# Output.net
KiCad netlist of a schematic drawn in Altium Designer
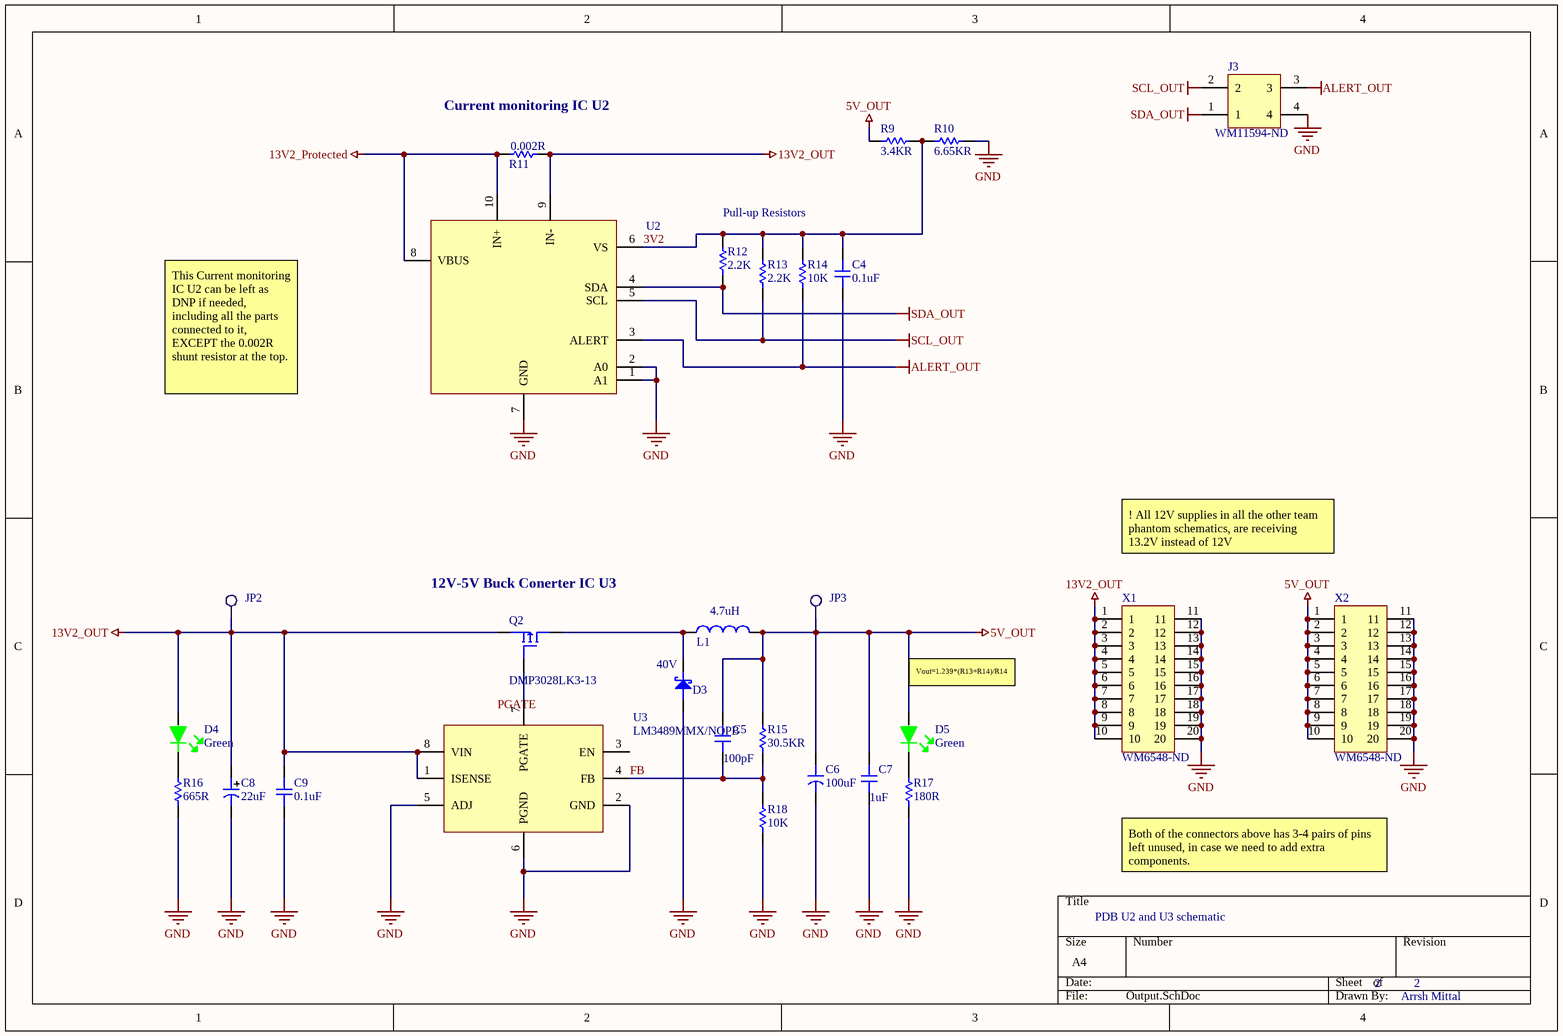
[diagram p0: Output.SchDoc]

(export (version "E")
  (design (tool "Eeschema 10.0.6"))
  (components
    (comp (ref "C4")
      (value "0.1uF")
      (footprint "CAP-0805")
      (description "CAP CER 0.1UF 16V Y5V 0805")
      (fields
        (field (name "MANUFACTURER") "KEMET")
        (field (name "MANUFACTURER PART NUMBER") "C0805C104Z4VACTU")
      )
      (libsource (lib "Capacitors") (part "0805-0.1uF-16V"))
    )
    (comp (ref "C5")
      (value "100pF")
      (description "0603 100 pF 50 V ±5% Tolerance C0G/NP0 SMT Multilayer Ceramic Capacitor")
      (fields
        (field (name "MANUFACTURER") "Kyocera AVX")
        (field (name "MANUFACTURER PART NUMBER") "06035A101JAT2~{A}4K")
      )
      (libsource (lib "Capacitors") (part "0603-100pF-50V"))
    )
    (comp (ref "C6")
      (value "100uF")
      (footprint "CAP-1411")
      (description "CAP TANT 100UF 10% 6.3V 1411")
      (fields
        (field (name "MANUFACTURER") "KEMET")
        (field (name "MANUFACTURER PART NUMBER") "T495B107K006ATE400")
      )
      (libsource (lib "Capacitors") (part "1411-100uF-6.3V"))
    )
    (comp (ref "C7")
      (value "1uF")
      (footprint "CAP-0603")
      (description "CAP CER 1UF 16V X7R 0603")
      (fields
        (field (name "MANUFACTURER") "KEMET")
        (field (name "MANUFACTURER PART NUMBER") "C0603C105K4RACTU")
      )
      (libsource (lib "Capacitors") (part "0603-1uF-16V"))
    )
    (comp (ref "C8")
      (value "22uF")
      (description "Aluminum Electrolytic Capacitors - SMD 22uF 50 Volts 20% LYTICS/IC")
      (fields
        (field (name "MANUFACTURER") "CDE Illinois Capacitor")
        (field (name "MANUFACTURER PART NUMBER") "226SML050M")
      )
      (libsource (lib "Capacitors") (part "AEC-22uF-50V"))
    )
    (comp (ref "C9")
      (value "0.1uF")
      (footprint "CAP-0805")
      (description "CAP CER 0.1UF 50V Y5V 0805")
      (fields
        (field (name "MANUFACTURER") "KEMET")
        (field (name "MANUFACTURER PART NUMBER") "C0805C104Z5VACTU")
      )
      (libsource (lib "Capacitors") (part "0805-0.1uF-50V"))
    )
    (comp (ref "D3")
      (value "40V")
      (description "DIODE SCHOTTKY 40V 8A DO214AB")
      (fields (field (name "MANUFACTURER") "MCC") (field (name "MANUFACTURER PART NUMBER") "SK84L-TP"))
      (libsource (lib "Diodes") (part "Schottky-40V-8A"))
    )
    (comp (ref "D4")
      (value "Green")
      (footprint "LED-0603")
      (description "LED GREEN CLEAR 0603 SMD")
      (fields
        (field (name "MANUFACTURER") "Wurth Electronics")
        (field (name "MANUFACTURER PART NUMBER") "150060VS75000")
      )
      (libsource (lib "LEDs") (part "LED-Green"))
    )
    (comp (ref "D5")
      (value "Green")
      (footprint "LED-0603")
      (description "LED GREEN CLEAR 0603 SMD")
      (fields
        (field (name "MANUFACTURER") "Wurth Electronics")
        (field (name "MANUFACTURER PART NUMBER") "150060VS75000")
      )
      (libsource (lib "LEDs") (part "LED-Green"))
    )
    (comp (ref "J3")
      (value "WM11594-ND")
      (footprint "2X2PIN")
      (description "CONN HEADER R/A 4POS 3.5MM")
      (fields (field (name "MANUFACTURER") "Molex") (field (name "MANUFACTURER PART NUMBER") "172316-1104"))
      (libsource (lib "Connectors") (part "2X2PIN"))
    )
    (comp (ref "JP2")
      (value "Testpoint2")
      (footprint "TP2")
      (description "Single layer pad TP")
      (libsource (lib "Misc") (part "Testpoint2"))
    )
    (comp (ref "JP3")
      (value "Testpoint2")
      (footprint "TP2")
      (description "Single layer pad TP")
      (libsource (lib "Misc") (part "Testpoint2"))
    )
    (comp (ref "L1")
      (value "4.7uH")
      (description "FIXED IND 4.7UH 10A 15.5 MOHM")
      (fields (field (name "MANUFACTURER") "Pulse") (field (name "MANUFACTURER PART NUMBER") "PA4342.472NLT"))
      (libsource (lib "Inductors") (part "4.7uH-10A"))
    )
    (comp (ref "Q2")
      (value "DMP3028LK3-13")
      (footprint "DPAK228P990X239-4N")
      (description "MOSFET P-CH 30V 27A TO252")
      (fields (field (name "MANUFACTURER") "Diodes"))
      (libsource (lib "Transistors") (part "P-FET-30V-27A"))
    )
    (comp (ref "R9")
      (value "3.4KR")
      (footprint "RESC1608X50N")
      (description "Res Thin Film 0603 3.4K Ohm 0.1% 1/10W ±25ppm/°C Molded SMD Paper T/R")
      (fields
        (field (name "MANUFACTURER") "TE Connectivity")
        (field (name "MANUFACTURER PART NUMBER") "RP73PF1J3K4BTDF")
      )
      (libsource (lib "Resistors") (part "0603-3.4KR"))
    )
    (comp (ref "R10")
      (value "6.65KR")
      (footprint "RESC1608X50N")
      (description "RES SMD 6.65K OHM 0.1% 1/6W 0603")
      (fields
        (field (name "MANUFACTURER") "TE Connectivity")
        (field (name "MANUFACTURER PART NUMBER") "8-2176088-4")
      )
      (libsource (lib "Resistors") (part "0603-6.65KR"))
    )
    (comp (ref "R11")
      (value "0.002R")
      (footprint "2512")
      (fields
        (field (name "MANUFACTURER") "Bourns")
        (field (name "MANUFACTURER PART NUMBER") "CSS2H-2512K-2L00F")
        (field (name "TOLERANCE") "1%")
      )
      (libsource (lib "Resistors") (part "2512-0.002R-5W"))
    )
    (comp (ref "R12")
      (value "2.2K")
      (footprint "RES-0603")
      (description "RES SMD 2.2K OHM 1% 1/10W 0603")
      (fields
        (field (name "MANUFACTURER") "Yageo Phycomp")
        (field (name "MANUFACTURER PART NUMBER") "RC0603FR-072K2L")
      )
      (libsource (lib "Resistors") (part "0603-2.2KR"))
    )
    (comp (ref "R13")
      (value "2.2K")
      (footprint "RES-0603")
      (description "RES SMD 2.2K OHM 1% 1/10W 0603")
      (fields
        (field (name "MANUFACTURER") "Yageo Phycomp")
        (field (name "MANUFACTURER PART NUMBER") "RC0603FR-072K2L")
      )
      (libsource (lib "Resistors") (part "0603-2.2KR"))
    )
    (comp (ref "R14")
      (value "10K")
      (footprint "RES-0603")
      (description "RES SMD 10K OHM 5% 1/10W 0603")
      (fields
        (field (name "MANUFACTURER") "Yageo")
        (field (name "MANUFACTURER PART NUMBER") "RC0603JR-0710KL")
      )
      (libsource (lib "Resistors") (part "0603-10KR"))
    )
    (comp (ref "R15")
      (value "30.5KR")
      (description "RES 30.5K OHM 1% 1/16W 0402")
      (fields
        (field (name "MANUFACTURER") "KOA Speer")
        (field (name "MANUFACTURER PART NUMBER") "RN73R1ETTP3052F25")
      )
      (libsource (lib "Resistors") (part "0402-30.5KR"))
    )
    (comp (ref "R16")
      (value "665R")
      (footprint "RES-0603")
      (description "RES SMD 665 OHM 1% 1/10W 0603")
      (fields
        (field (name "MANUFACTURER") "Yageo")
        (field (name "MANUFACTURER PART NUMBER") "RC0603FR-07665RL")
      )
      (libsource (lib "Resistors") (part "0603-665R"))
    )
    (comp (ref "R17")
      (value "180R")
      (footprint "RES-0603")
      (description "RES SMD 180 OHM 1% 1/10W 0603")
      (fields
        (field (name "MANUFACTURER") "TE Connectivity")
        (field (name "MANUFACTURER PART NUMBER") "CRGCQ0603F180R")
      )
      (libsource (lib "Resistors") (part "0603-180R"))
    )
    (comp (ref "R18")
      (value "10K")
      (footprint "RES-0402")
      (description "RES 10K OHM 1% 1/10W 0402")
      (fields
        (field (name "MANUFACTURER") "KOA Speer")
        (field (name "MANUFACTURER PART NUMBER") "RK73H1ETTP1002F")
      )
      (libsource (lib "Resistors") (part "0402-10KR"))
    )
    (comp (ref "U2")
      (value "INA226AIDGSR")
      (footprint "SOP50P490X110-10N:SOP50P490X110-10N")
      (description "Bi Directional Current and Power Monitor 10-Pin VSSOP T/R")
      (fields (field (name "MANUFACTURER") "Texas Instruments"))
      (libsource (lib "ICs") (part "INA226AIDGSR"))
    )
    (comp (ref "U3")
      (value "LM3489MMX/NOPB")
      (footprint "SOP65P490X110-8N")
      (description "DC DC Cntrlr Single-OUT Buck 4.5V to 35V Input 8-Pin VSSOP T/R")
      (fields (field (name "MANUFACTURER") "TI National Semiconductor"))
      (libsource (lib "ICs") (part "LM3489MMX/NOPB"))
    )
    (comp (ref "X1")
      (value "WM6548-ND")
      (footprint "MOLEX_20pin(RECT)")
      (description "Connector Header Through Hole 20 position 0.100\" (2.54mm)")
      (fields (field (name "SUPPLIER PART NUMBER 1") "WM6548-ND"))
      (libsource (lib "Connectors") (part "RECT_MOLEX_20pin"))
    )
    (comp (ref "X2")
      (value "WM6548-ND")
      (footprint "MOLEX_20pin(RECT)")
      (description "Connector Header Through Hole 20 position 0.100\" (2.54mm)")
      (fields (field (name "SUPPLIER PART NUMBER 1") "WM6548-ND"))
      (libsource (lib "Connectors") (part "RECT_MOLEX_20pin"))
    )
  )
  (nets
    (net (code "1") (name "/3V2") (class "Default")
      (node (ref "C4") (pin "2") (pinfunction "2_2") (pintype "passive"))
      (node (ref "R10") (pin "1") (pinfunction "1_1") (pintype "passive"))
      (node (ref "R12") (pin "2") (pinfunction "2_2") (pintype "passive"))
      (node (ref "R13") (pin "2") (pinfunction "2_2") (pintype "passive"))
      (node (ref "R14") (pin "2") (pinfunction "2_2") (pintype "passive"))
      (node (ref "R9") (pin "2") (pinfunction "2_2") (pintype "passive"))
      (node (ref "U2") (pin "6") (pinfunction "VS_6") (pintype "power_in"))
    )
    (net (code "3") (name "/FB") (class "Default")
      (node (ref "C5") (pin "1") (pinfunction "1_1") (pintype "passive"))
      (node (ref "R15") (pin "1") (pinfunction "1_1") (pintype "passive"))
      (node (ref "R18") (pin "2") (pinfunction "2_2") (pintype "passive"))
      (node (ref "U3") (pin "4") (pinfunction "FB_4") (pintype "power_in"))
    )
    (net (code "4") (name "5V_OUT") (class "Default")
      (node (ref "C5") (pin "2") (pinfunction "2_2") (pintype "passive"))
      (node (ref "C6") (pin "2") (pinfunction "2_2") (pintype "passive"))
      (node (ref "C7") (pin "2") (pinfunction "2_2") (pintype "passive"))
      (node (ref "D5") (pin "1") (pinfunction "1_1") (pintype "passive"))
      (node (ref "JP3") (pin "1") (pinfunction "1_1") (pintype "passive"))
      (node (ref "L1") (pin "2") (pinfunction "2_2") (pintype "passive"))
      (node (ref "R15") (pin "2") (pinfunction "2_2") (pintype "passive"))
      (node (ref "R9") (pin "1") (pinfunction "1_1") (pintype "passive"))
      (node (ref "X2") (pin "1") (pinfunction "1_1") (pintype "passive"))
      (node (ref "X2") (pin "10") (pinfunction "10_10") (pintype "passive"))
      (node (ref "X2") (pin "2") (pinfunction "2_2") (pintype "passive"))
      (node (ref "X2") (pin "3") (pinfunction "3_3") (pintype "passive"))
      (node (ref "X2") (pin "4") (pinfunction "4_4") (pintype "passive"))
      (node (ref "X2") (pin "5") (pinfunction "5_5") (pintype "passive"))
      (node (ref "X2") (pin "6") (pinfunction "6_6") (pintype "passive"))
      (node (ref "X2") (pin "7") (pinfunction "7_7") (pintype "passive"))
      (node (ref "X2") (pin "8") (pinfunction "8_8") (pintype "passive"))
      (node (ref "X2") (pin "9") (pinfunction "9_9") (pintype "passive"))
    )
    (net (code "5") (name "13V2_OUT") (class "Default")
      (node (ref "C8") (pin "1") (pinfunction "1_1") (pintype "passive"))
      (node (ref "C9") (pin "2") (pinfunction "2_2") (pintype "passive"))
      (node (ref "D4") (pin "1") (pinfunction "1_1") (pintype "passive"))
      (node (ref "JP2") (pin "1") (pinfunction "1_1") (pintype "passive"))
      (node (ref "Q2") (pin "3") (pinfunction "3_3") (pintype "passive"))
      (node (ref "R11") (pin "1") (pinfunction "1_1") (pintype "passive"))
      (node (ref "U2") (pin "9") (pinfunction "IN-_9") (pintype "power_in"))
      (node (ref "U3") (pin "1") (pinfunction "ISENSE_1") (pintype "power_in"))
      (node (ref "U3") (pin "8") (pinfunction "VIN_8") (pintype "power_in"))
      (node (ref "X1") (pin "1") (pinfunction "1_1") (pintype "passive"))
      (node (ref "X1") (pin "10") (pinfunction "10_10") (pintype "passive"))
      (node (ref "X1") (pin "2") (pinfunction "2_2") (pintype "passive"))
      (node (ref "X1") (pin "3") (pinfunction "3_3") (pintype "passive"))
      (node (ref "X1") (pin "4") (pinfunction "4_4") (pintype "passive"))
      (node (ref "X1") (pin "5") (pinfunction "5_5") (pintype "passive"))
      (node (ref "X1") (pin "6") (pinfunction "6_6") (pintype "passive"))
      (node (ref "X1") (pin "7") (pinfunction "7_7") (pintype "passive"))
      (node (ref "X1") (pin "8") (pinfunction "8_8") (pintype "passive"))
      (node (ref "X1") (pin "9") (pinfunction "9_9") (pintype "passive"))
    )
    (net (code "6") (name "13V2_Protected") (class "Default")
      (node (ref "R11") (pin "2") (pinfunction "2_2") (pintype "passive"))
      (node (ref "U2") (pin "10") (pinfunction "IN+_10") (pintype "power_in"))
      (node (ref "U2") (pin "8") (pinfunction "VBUS_8") (pintype "power_in"))
    )
    (net (code "7") (name "ALERT_OUT") (class "Default")
      (node (ref "J3") (pin "3") (pinfunction "3_3") (pintype "passive"))
      (node (ref "R14") (pin "1") (pinfunction "1_1") (pintype "passive"))
      (node (ref "U2") (pin "3") (pinfunction "ALERT_3") (pintype "power_in"))
    )
    (net (code "8") (name "GND") (class "Default")
      (node (ref "C4") (pin "1") (pinfunction "1_1") (pintype "passive"))
      (node (ref "C6") (pin "1") (pinfunction "1_1") (pintype "passive"))
      (node (ref "C7") (pin "1") (pinfunction "1_1") (pintype "passive"))
      (node (ref "C8") (pin "2") (pinfunction "2_2") (pintype "passive"))
      (node (ref "C9") (pin "1") (pinfunction "1_1") (pintype "passive"))
      (node (ref "D3") (pin "2") (pinfunction "2_2") (pintype "passive"))
      (node (ref "J3") (pin "4") (pinfunction "4_4") (pintype "passive"))
      (node (ref "R10") (pin "2") (pinfunction "2_2") (pintype "passive"))
      (node (ref "R16") (pin "1") (pinfunction "1_1") (pintype "passive"))
      (node (ref "R17") (pin "1") (pinfunction "1_1") (pintype "passive"))
      (node (ref "R18") (pin "1") (pinfunction "1_1") (pintype "passive"))
      (node (ref "U2") (pin "1") (pinfunction "A1_1") (pintype "power_in"))
      (node (ref "U2") (pin "2") (pinfunction "A0_2") (pintype "power_in"))
      (node (ref "U2") (pin "7") (pinfunction "GND_7") (pintype "power_in"))
      (node (ref "U3") (pin "2") (pinfunction "GND_2") (pintype "power_in"))
      (node (ref "U3") (pin "5") (pinfunction "ADJ_5") (pintype "power_in"))
      (node (ref "U3") (pin "6") (pinfunction "PGND_6") (pintype "power_in"))
      (node (ref "X1") (pin "11") (pinfunction "11_11") (pintype "passive"))
      (node (ref "X1") (pin "12") (pinfunction "12_12") (pintype "passive"))
      (node (ref "X1") (pin "13") (pinfunction "13_13") (pintype "passive"))
      (node (ref "X1") (pin "14") (pinfunction "14_14") (pintype "passive"))
      (node (ref "X1") (pin "15") (pinfunction "15_15") (pintype "passive"))
      (node (ref "X1") (pin "16") (pinfunction "16_16") (pintype "passive"))
      (node (ref "X1") (pin "17") (pinfunction "17_17") (pintype "passive"))
      (node (ref "X1") (pin "18") (pinfunction "18_18") (pintype "passive"))
      (node (ref "X1") (pin "19") (pinfunction "19_19") (pintype "passive"))
      (node (ref "X1") (pin "20") (pinfunction "20_20") (pintype "passive"))
      (node (ref "X2") (pin "11") (pinfunction "11_11") (pintype "passive"))
      (node (ref "X2") (pin "12") (pinfunction "12_12") (pintype "passive"))
      (node (ref "X2") (pin "13") (pinfunction "13_13") (pintype "passive"))
      (node (ref "X2") (pin "14") (pinfunction "14_14") (pintype "passive"))
      (node (ref "X2") (pin "15") (pinfunction "15_15") (pintype "passive"))
      (node (ref "X2") (pin "16") (pinfunction "16_16") (pintype "passive"))
      (node (ref "X2") (pin "17") (pinfunction "17_17") (pintype "passive"))
      (node (ref "X2") (pin "18") (pinfunction "18_18") (pintype "passive"))
      (node (ref "X2") (pin "19") (pinfunction "19_19") (pintype "passive"))
      (node (ref "X2") (pin "20") (pinfunction "20_20") (pintype "passive"))
    )
    (net (code "9") (name "Net-(D3-Pad1)") (class "Default")
      (node (ref "D3") (pin "1") (pinfunction "1_1") (pintype "passive"))
      (node (ref "L1") (pin "1") (pinfunction "1_1") (pintype "passive"))
      (node (ref "Q2") (pin "2") (pinfunction "2_2") (pintype "passive"))
    )
    (net (code "10") (name "Net-(D4-Pad2)") (class "Default")
      (node (ref "D4") (pin "2") (pinfunction "2_2") (pintype "passive"))
      (node (ref "R16") (pin "2") (pinfunction "2_2") (pintype "passive"))
    )
    (net (code "11") (name "Net-(D5-Pad2)") (class "Default")
      (node (ref "D5") (pin "2") (pinfunction "2_2") (pintype "passive"))
      (node (ref "R17") (pin "2") (pinfunction "2_2") (pintype "passive"))
    )
    (net (code "12") (name "Net-(U3-PGATE)") (class "Default")
      (node (ref "Q2") (pin "1") (pinfunction "1_1") (pintype "passive"))
      (node (ref "U3") (pin "7") (pinfunction "PGATE_7") (pintype "power_in"))
    )
    (net (code "13") (name "SCL_OUT") (class "Default")
      (node (ref "J3") (pin "2") (pinfunction "2_2") (pintype "passive"))
      (node (ref "R13") (pin "1") (pinfunction "1_1") (pintype "passive"))
      (node (ref "U2") (pin "5") (pinfunction "SCL_5") (pintype "power_in"))
    )
    (net (code "14") (name "SDA_OUT") (class "Default")
      (node (ref "J3") (pin "1") (pinfunction "1_1") (pintype "passive"))
      (node (ref "R12") (pin "1") (pinfunction "1_1") (pintype "passive"))
      (node (ref "U2") (pin "4") (pinfunction "SDA_4") (pintype "power_in"))
    )
    (net (code "15") (name "unconnected-(U3-EN-Pad3)") (class "Default")
      (node (ref "U3") (pin "3") (pinfunction "EN_3") (pintype "power_in"))
    )
  )
)
